# AMC_BOX_Backplane.net
KiCad netlist of a schematic drawn in Altium Designer
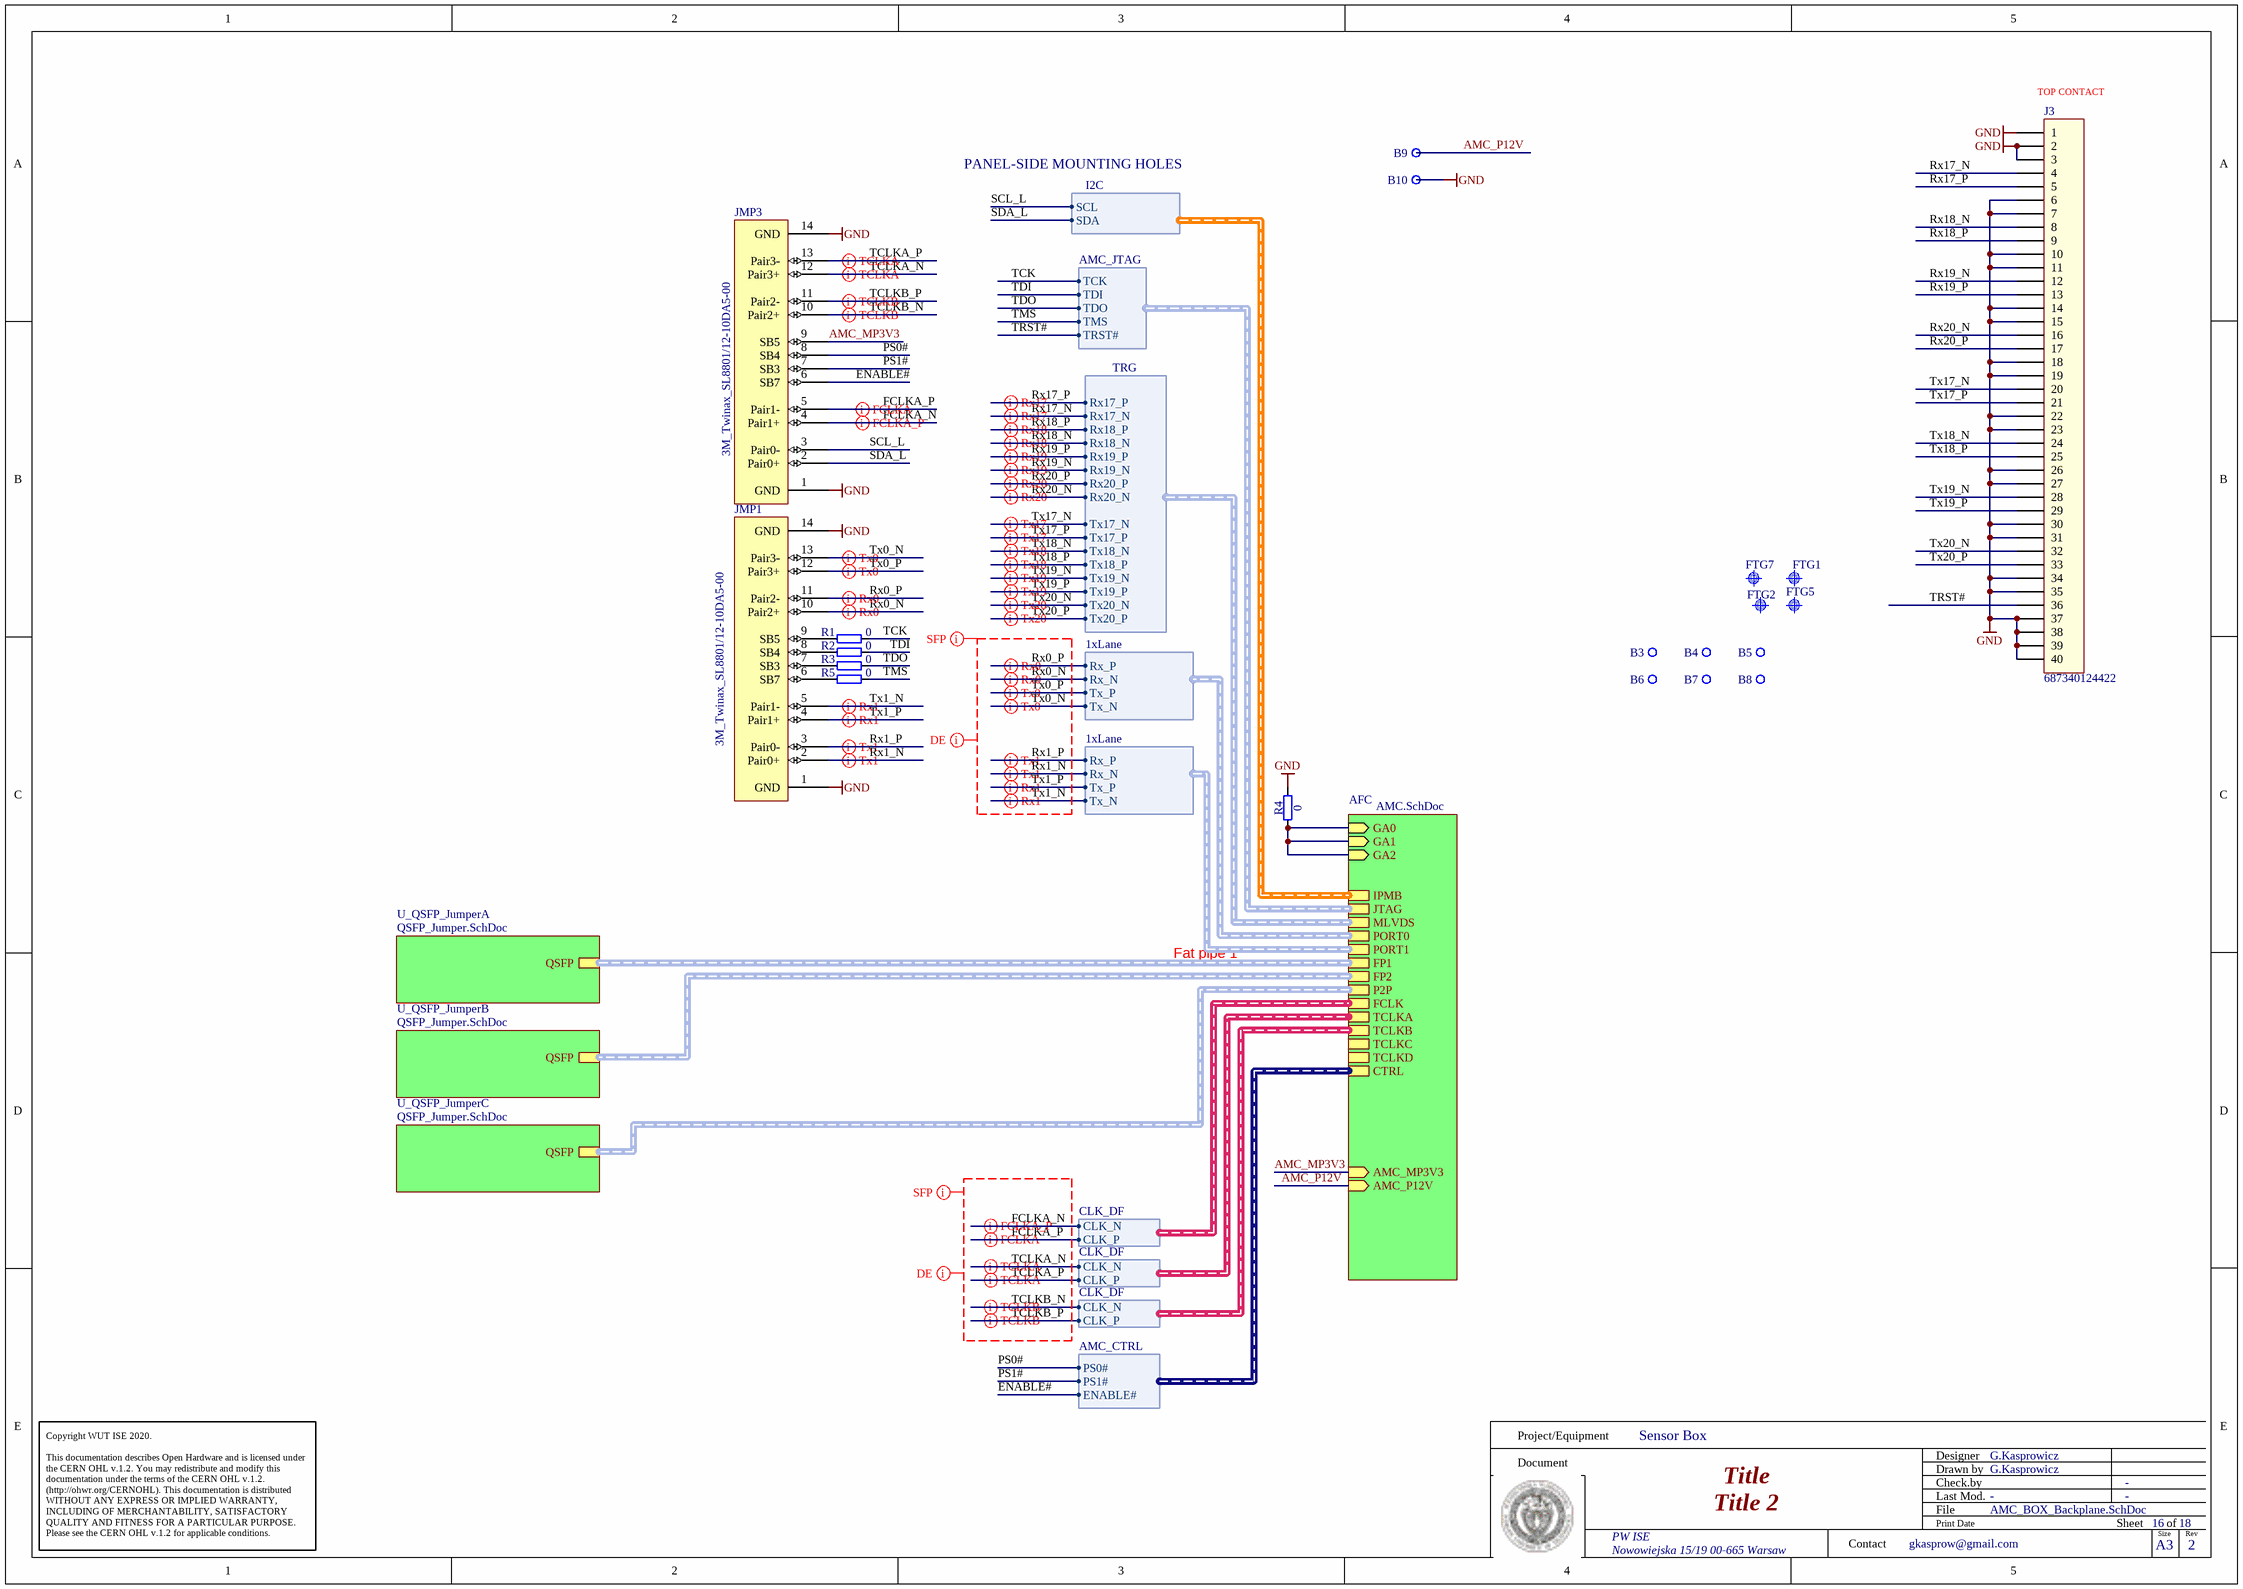
[diagram p0: AMC_BOX_Backplane.SchDoc]

(export (version "E")
  (design (tool "Eeschema 10.0.6"))
  (components
    (comp (ref "B3")
      (value "Plated Hole")
      (footprint "MTG320_550")
      (description "Single Terminal Socket")
      (fields (field (name "PART NUMBER") "PLATED_HOLE3.2_PAD5.5") (field (name "AUTHOR") "CERN DEM JMW"))
      (libsource (lib "Eletro-mechanical") (part "Single Terminal Socket"))
    )
    (comp (ref "B4")
      (value "Plated Hole")
      (footprint "MTG320_550")
      (description "Single Terminal Socket")
      (fields (field (name "PART NUMBER") "PLATED_HOLE3.2_PAD5.5") (field (name "AUTHOR") "CERN DEM JMW"))
      (libsource (lib "Eletro-mechanical") (part "Single Terminal Socket"))
    )
    (comp (ref "B5")
      (value "Plated Hole")
      (footprint "MTG320_550")
      (description "Single Terminal Socket")
      (fields (field (name "PART NUMBER") "PLATED_HOLE3.2_PAD5.5") (field (name "AUTHOR") "CERN DEM JMW"))
      (libsource (lib "Eletro-mechanical") (part "Single Terminal Socket"))
    )
    (comp (ref "B6")
      (value "Plated Hole")
      (footprint "MTG320_550")
      (description "Single Terminal Socket")
      (fields (field (name "PART NUMBER") "PLATED_HOLE3.2_PAD5.5") (field (name "AUTHOR") "CERN DEM JMW"))
      (libsource (lib "Eletro-mechanical") (part "Single Terminal Socket"))
    )
    (comp (ref "B7")
      (value "Plated Hole")
      (footprint "MTG320_550")
      (description "Single Terminal Socket")
      (fields (field (name "PART NUMBER") "PLATED_HOLE3.2_PAD5.5") (field (name "AUTHOR") "CERN DEM JMW"))
      (libsource (lib "Eletro-mechanical") (part "Single Terminal Socket"))
    )
    (comp (ref "B8")
      (value "Plated Hole")
      (footprint "MTG320_550")
      (description "Single Terminal Socket")
      (fields (field (name "PART NUMBER") "PLATED_HOLE3.2_PAD5.5") (field (name "AUTHOR") "CERN DEM JMW"))
      (libsource (lib "Eletro-mechanical") (part "Single Terminal Socket"))
    )
    (comp (ref "B9")
      (value "Plated Hole")
      (footprint "c200h150")
      (description "Single Terminal Socket")
      (fields (field (name "PART NUMBER") "PLATED_HOLE1.5_PAD2.0") (field (name "AUTHOR") "CERN DEM JLC"))
      (libsource (lib "Eletro-mechanical") (part "Single Terminal Socket"))
    )
    (comp (ref "B10")
      (value "Plated Hole")
      (footprint "c200h150")
      (description "Single Terminal Socket")
      (fields (field (name "PART NUMBER") "PLATED_HOLE1.5_PAD2.0") (field (name "AUTHOR") "CERN DEM JLC"))
      (libsource (lib "Eletro-mechanical") (part "Single Terminal Socket"))
    )
    (comp (ref "FTG1")
      (value "Use only in PCB")
      (footprint "FIDUCIAL_TOP_S100-200")
      (description "Fiducial Target")
      (fields (field (name "PART NUMBER") "FIDUCIAL_TARGET_S100-200") (field (name "AUTHOR") "CERN DEM JLC"))
      (libsource (lib "Eletro-mechanical") (part "Fiducial Target"))
    )
    (comp (ref "FTG2")
      (value "Use only in PCB")
      (footprint "FIDUCIAL_TOP_S100-200")
      (description "Fiducial Target")
      (fields (field (name "PART NUMBER") "FIDUCIAL_TARGET_S100-200") (field (name "AUTHOR") "CERN DEM JLC"))
      (libsource (lib "Eletro-mechanical") (part "Fiducial Target"))
    )
    (comp (ref "FTG5")
      (value "Use only in PCB")
      (footprint "FIDUCIAL_TOP_S100-200")
      (description "Fiducial Target")
      (fields (field (name "PART NUMBER") "FIDUCIAL_TARGET_S100-200") (field (name "AUTHOR") "CERN DEM JLC"))
      (libsource (lib "Eletro-mechanical") (part "Fiducial Target"))
    )
    (comp (ref "FTG7")
      (value "Use only in PCB")
      (footprint "FIDUCIAL_TOP_S100-200")
      (description "Fiducial Target")
      (fields (field (name "PART NUMBER") "FIDUCIAL_TARGET_S100-200") (field (name "AUTHOR") "CERN DEM JLC"))
      (libsource (lib "Eletro-mechanical") (part "Fiducial Target"))
    )
    (comp (ref "J3")
      (value "687340124422")
      (footprint "687340124422")
      (description "0.50 mm SMT ZIF Vertical WR-FPC, 40 pins")
      (fields (field (name "PUBLISHER") "Wurth Elektronik"))
      (libsource (lib "Altium_FPC_CONNECTORS (rev17a)") (part "687340124422"))
    )
    (comp (ref "JMP1")
      (value "3M_Twinax_SL8801/12-10DA5-00")
      (footprint "3M_Twinax_SL8801/12-10DA5-00")
      (libsource (lib "LIBRARY_SCH") (part "CBL_TWINAX_3M_4pairs_SB"))
    )
    (comp (ref "JMP3")
      (value "3M_Twinax_SL8801/12-10DA5-00")
      (footprint "3M_Twinax_SL8801/12-10DA5-00")
      (libsource (lib "LIBRARY_SCH") (part "CBL_TWINAX_3M_4pairs_SB"))
    )
    (comp (ref "R1")
      (value "0")
      (footprint "RESC1005X40N")
      (description "Resistor")
      (fields
        (field (name "PART NUMBER") "R0402_0R_JUMPER")
        (field (name "MANUFACTURER") "GENERIC")
        (field (name "AUTHOR") "CERN DEM JLC")
      )
      (libsource (lib "Resistors") (part "Resistor"))
    )
    (comp (ref "R2")
      (value "0")
      (footprint "RESC1005X40N")
      (description "Resistor")
      (fields
        (field (name "PART NUMBER") "R0402_0R_JUMPER")
        (field (name "MANUFACTURER") "GENERIC")
        (field (name "AUTHOR") "CERN DEM JLC")
      )
      (libsource (lib "Resistors") (part "Resistor"))
    )
    (comp (ref "R3")
      (value "0")
      (footprint "RESC1005X40N")
      (description "Resistor")
      (fields
        (field (name "PART NUMBER") "R0402_0R_JUMPER")
        (field (name "MANUFACTURER") "GENERIC")
        (field (name "AUTHOR") "CERN DEM JLC")
      )
      (libsource (lib "Resistors") (part "Resistor"))
    )
    (comp (ref "R4")
      (value "0")
      (footprint "RESC1005X40N")
      (description "Resistor")
      (fields
        (field (name "PART NUMBER") "R0402_0R_JUMPER")
        (field (name "MANUFACTURER") "GENERIC")
        (field (name "AUTHOR") "CERN DEM JLC")
      )
      (libsource (lib "Resistors") (part "Resistor"))
    )
    (comp (ref "R5")
      (value "0")
      (footprint "RESC1005X40N")
      (description "Resistor")
      (fields
        (field (name "PART NUMBER") "R0402_0R_JUMPER")
        (field (name "MANUFACTURER") "GENERIC")
        (field (name "AUTHOR") "CERN DEM JLC")
      )
      (libsource (lib "Resistors") (part "Resistor"))
    )
  )
  (nets
    (net (code "7") (name "/AMC_MP3V3") (class "Default")
      (node (ref "JMP3") (pin "9") (pinfunction "SB5_9") (pintype "bidirectional"))
    )
    (net (code "8") (name "/AMC_P12V") (class "Default")
      (node (ref "B9") (pin "1") (pinfunction "1_1") (pintype "bidirectional"))
    )
    (net (code "9") (name "/ENABLE#") (class "Default")
      (node (ref "JMP3") (pin "6") (pinfunction "SB7_6") (pintype "bidirectional"))
    )
    (net (code "10") (name "/FCLKA_N") (class "Default")
      (node (ref "JMP3") (pin "4") (pinfunction "Pair1+_4") (pintype "bidirectional"))
    )
    (net (code "11") (name "/FCLKA_P") (class "Default")
      (node (ref "JMP3") (pin "5") (pinfunction "Pair1-_5") (pintype "bidirectional"))
    )
    (net (code "14") (name "/GA0") (class "Default")
      (node (ref "R4") (pin "1") (pinfunction "1_1") (pintype "passive"))
    )
    (net (code "16") (name "/PS0#") (class "Default")
      (node (ref "JMP3") (pin "8") (pinfunction "SB4_8") (pintype "bidirectional"))
    )
    (net (code "17") (name "/PS1#") (class "Default")
      (node (ref "JMP3") (pin "7") (pinfunction "SB3_7") (pintype "bidirectional"))
    )
    (net (code "18") (name "/Rx0_N") (class "Default")
      (node (ref "JMP1") (pin "10") (pinfunction "Pair2+_10") (pintype "bidirectional"))
    )
    (net (code "19") (name "/Rx0_P") (class "Default")
      (node (ref "JMP1") (pin "11") (pinfunction "Pair2-_11") (pintype "bidirectional"))
    )
    (net (code "20") (name "/Rx1_N") (class "Default")
      (node (ref "JMP1") (pin "2") (pinfunction "Pair0+_2") (pintype "bidirectional"))
    )
    (net (code "21") (name "/Rx1_P") (class "Default")
      (node (ref "JMP1") (pin "3") (pinfunction "Pair0-_3") (pintype "bidirectional"))
    )
    (net (code "22") (name "/Rx17_N") (class "Default")
      (node (ref "J3") (pin "4") (pinfunction "4_4") (pintype "passive"))
    )
    (net (code "23") (name "/Rx17_P") (class "Default")
      (node (ref "J3") (pin "5") (pinfunction "5_5") (pintype "passive"))
    )
    (net (code "24") (name "/Rx18_N") (class "Default")
      (node (ref "J3") (pin "8") (pinfunction "8_8") (pintype "passive"))
    )
    (net (code "25") (name "/Rx18_P") (class "Default")
      (node (ref "J3") (pin "9") (pinfunction "9_9") (pintype "passive"))
    )
    (net (code "26") (name "/Rx19_N") (class "Default")
      (node (ref "J3") (pin "12") (pinfunction "12_12") (pintype "passive"))
    )
    (net (code "27") (name "/Rx19_P") (class "Default")
      (node (ref "J3") (pin "13") (pinfunction "13_13") (pintype "passive"))
    )
    (net (code "28") (name "/Rx20_N") (class "Default")
      (node (ref "J3") (pin "16") (pinfunction "16_16") (pintype "passive"))
    )
    (net (code "29") (name "/Rx20_P") (class "Default")
      (node (ref "J3") (pin "17") (pinfunction "17_17") (pintype "passive"))
    )
    (net (code "30") (name "/SCL_L") (class "Default")
      (node (ref "JMP3") (pin "3") (pinfunction "Pair0-_3") (pintype "bidirectional"))
    )
    (net (code "31") (name "/SDA_L") (class "Default")
      (node (ref "JMP3") (pin "2") (pinfunction "Pair0+_2") (pintype "bidirectional"))
    )
    (net (code "32") (name "/TCK") (class "Default")
      (node (ref "R1") (pin "2") (pinfunction "2_2") (pintype "passive"))
    )
    (net (code "33") (name "/TCLKA_N") (class "Default")
      (node (ref "JMP3") (pin "12") (pinfunction "Pair3+_12") (pintype "bidirectional"))
    )
    (net (code "34") (name "/TCLKA_P") (class "Default")
      (node (ref "JMP3") (pin "13") (pinfunction "Pair3-_13") (pintype "bidirectional"))
    )
    (net (code "35") (name "/TCLKB_N") (class "Default")
      (node (ref "JMP3") (pin "10") (pinfunction "Pair2+_10") (pintype "bidirectional"))
    )
    (net (code "36") (name "/TCLKB_P") (class "Default")
      (node (ref "JMP3") (pin "11") (pinfunction "Pair2-_11") (pintype "bidirectional"))
    )
    (net (code "39") (name "/TDI") (class "Default")
      (node (ref "R2") (pin "2") (pinfunction "2_2") (pintype "passive"))
    )
    (net (code "40") (name "/TDO") (class "Default")
      (node (ref "R3") (pin "2") (pinfunction "2_2") (pintype "passive"))
    )
    (net (code "41") (name "/TMS") (class "Default")
      (node (ref "R5") (pin "2") (pinfunction "2_2") (pintype "passive"))
    )
    (net (code "42") (name "/TRST#") (class "Default")
      (node (ref "J3") (pin "36") (pinfunction "36_36") (pintype "passive"))
    )
    (net (code "43") (name "/Tx0_N") (class "Default")
      (node (ref "JMP1") (pin "13") (pinfunction "Pair3-_13") (pintype "bidirectional"))
    )
    (net (code "44") (name "/Tx0_P") (class "Default")
      (node (ref "JMP1") (pin "12") (pinfunction "Pair3+_12") (pintype "bidirectional"))
    )
    (net (code "45") (name "/Tx1_N") (class "Default")
      (node (ref "JMP1") (pin "5") (pinfunction "Pair1-_5") (pintype "bidirectional"))
    )
    (net (code "46") (name "/Tx1_P") (class "Default")
      (node (ref "JMP1") (pin "4") (pinfunction "Pair1+_4") (pintype "bidirectional"))
    )
    (net (code "47") (name "/Tx17_N") (class "Default")
      (node (ref "J3") (pin "20") (pinfunction "20_20") (pintype "passive"))
    )
    (net (code "48") (name "/Tx17_P") (class "Default")
      (node (ref "J3") (pin "21") (pinfunction "21_21") (pintype "passive"))
    )
    (net (code "49") (name "/Tx18_N") (class "Default")
      (node (ref "J3") (pin "24") (pinfunction "24_24") (pintype "passive"))
    )
    (net (code "50") (name "/Tx18_P") (class "Default")
      (node (ref "J3") (pin "25") (pinfunction "25_25") (pintype "passive"))
    )
    (net (code "51") (name "/Tx19_N") (class "Default")
      (node (ref "J3") (pin "28") (pinfunction "28_28") (pintype "passive"))
    )
    (net (code "52") (name "/Tx19_P") (class "Default")
      (node (ref "J3") (pin "29") (pinfunction "29_29") (pintype "passive"))
    )
    (net (code "53") (name "/Tx20_N") (class "Default")
      (node (ref "J3") (pin "32") (pinfunction "32_32") (pintype "passive"))
    )
    (net (code "54") (name "/Tx20_P") (class "Default")
      (node (ref "J3") (pin "33") (pinfunction "33_33") (pintype "passive"))
    )
    (net (code "61") (name "GND") (class "Default")
      (node (ref "B10") (pin "1") (pinfunction "1_1") (pintype "bidirectional"))
      (node (ref "J3") (pin "1") (pinfunction "1_1") (pintype "passive"))
      (node (ref "J3") (pin "10") (pinfunction "10_10") (pintype "passive"))
      (node (ref "J3") (pin "11") (pinfunction "11_11") (pintype "passive"))
      (node (ref "J3") (pin "14") (pinfunction "14_14") (pintype "passive"))
      (node (ref "J3") (pin "15") (pinfunction "15_15") (pintype "passive"))
      (node (ref "J3") (pin "18") (pinfunction "18_18") (pintype "passive"))
      (node (ref "J3") (pin "19") (pinfunction "19_19") (pintype "passive"))
      (node (ref "J3") (pin "2") (pinfunction "2_2") (pintype "passive"))
      (node (ref "J3") (pin "22") (pinfunction "22_22") (pintype "passive"))
      (node (ref "J3") (pin "23") (pinfunction "23_23") (pintype "passive"))
      (node (ref "J3") (pin "26") (pinfunction "26_26") (pintype "passive"))
      (node (ref "J3") (pin "27") (pinfunction "27_27") (pintype "passive"))
      (node (ref "J3") (pin "3") (pinfunction "3_3") (pintype "passive"))
      (node (ref "J3") (pin "30") (pinfunction "30_30") (pintype "passive"))
      (node (ref "J3") (pin "31") (pinfunction "31_31") (pintype "passive"))
      (node (ref "J3") (pin "34") (pinfunction "34_34") (pintype "passive"))
      (node (ref "J3") (pin "35") (pinfunction "35_35") (pintype "passive"))
      (node (ref "J3") (pin "37") (pinfunction "37_37") (pintype "passive"))
      (node (ref "J3") (pin "38") (pinfunction "38_38") (pintype "passive"))
      (node (ref "J3") (pin "39") (pinfunction "39_39") (pintype "passive"))
      (node (ref "J3") (pin "40") (pinfunction "40_40") (pintype "passive"))
      (node (ref "J3") (pin "6") (pinfunction "6_6") (pintype "passive"))
      (node (ref "J3") (pin "7") (pinfunction "7_7") (pintype "passive"))
      (node (ref "JMP1") (pin "1") (pinfunction "GND_1") (pintype "power_in"))
      (node (ref "JMP1") (pin "14") (pinfunction "GND_14") (pintype "power_in"))
      (node (ref "JMP3") (pin "1") (pinfunction "GND_1") (pintype "power_in"))
      (node (ref "JMP3") (pin "14") (pinfunction "GND_14") (pintype "power_in"))
      (node (ref "R4") (pin "2") (pinfunction "2_2") (pintype "passive"))
    )
    (net (code "62") (name "Net-(JMP1-SB3)") (class "Default")
      (node (ref "JMP1") (pin "7") (pinfunction "SB3_7") (pintype "bidirectional"))
      (node (ref "R3") (pin "1") (pinfunction "1_1") (pintype "passive"))
    )
    (net (code "63") (name "Net-(JMP1-SB4)") (class "Default")
      (node (ref "JMP1") (pin "8") (pinfunction "SB4_8") (pintype "bidirectional"))
      (node (ref "R2") (pin "1") (pinfunction "1_1") (pintype "passive"))
    )
    (net (code "64") (name "Net-(JMP1-SB5)") (class "Default")
      (node (ref "JMP1") (pin "9") (pinfunction "SB5_9") (pintype "bidirectional"))
      (node (ref "R1") (pin "1") (pinfunction "1_1") (pintype "passive"))
    )
    (net (code "65") (name "Net-(JMP1-SB7)") (class "Default")
      (node (ref "JMP1") (pin "6") (pinfunction "SB7_6") (pintype "bidirectional"))
      (node (ref "R5") (pin "1") (pinfunction "1_1") (pintype "passive"))
    )
    (net (code "66") (name "unconnected-(B3-Pad1)") (class "Default")
      (node (ref "B3") (pin "1") (pinfunction "1_1") (pintype "bidirectional"))
    )
    (net (code "67") (name "unconnected-(B4-Pad1)") (class "Default")
      (node (ref "B4") (pin "1") (pinfunction "1_1") (pintype "bidirectional"))
    )
    (net (code "68") (name "unconnected-(B5-Pad1)") (class "Default")
      (node (ref "B5") (pin "1") (pinfunction "1_1") (pintype "bidirectional"))
    )
    (net (code "69") (name "unconnected-(B6-Pad1)") (class "Default")
      (node (ref "B6") (pin "1") (pinfunction "1_1") (pintype "bidirectional"))
    )
    (net (code "70") (name "unconnected-(B7-Pad1)") (class "Default")
      (node (ref "B7") (pin "1") (pinfunction "1_1") (pintype "bidirectional"))
    )
    (net (code "71") (name "unconnected-(B8-Pad1)") (class "Default")
      (node (ref "B8") (pin "1") (pinfunction "1_1") (pintype "bidirectional"))
    )
  )
)
